# flyght.net
KiCad netlist of a schematic drawn in EAGLE
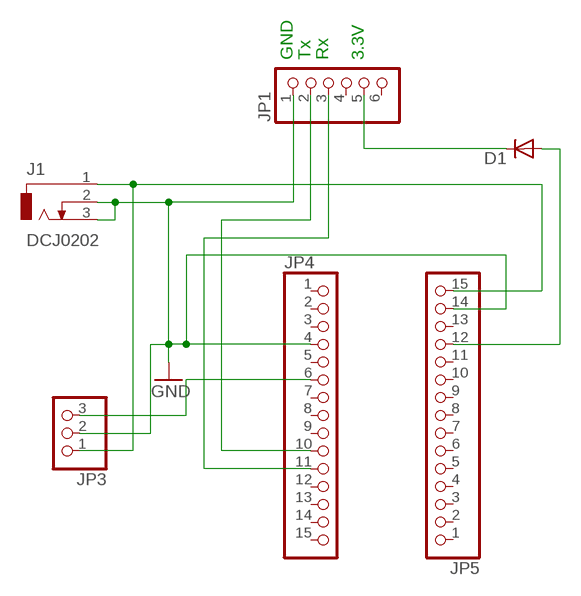
[diagram p0: schematic, sheet 1]

(export (version "E")
  (design (tool "Eeschema 10.0.6"))
  (components
    (comp (ref "D1")
      (value "1N4004")
      (footprint "eagle-import:DO41-10")
      (libsource (lib "eagle-import") (part "1N4004"))
    )
    (comp (ref "J1")
      (value "DCJ0202")
      (footprint "eagle-import:DCJ0202")
      (libsource (lib "eagle-import") (part "DCJ0202"))
    )
    (comp (ref "JP1")
      (value "PINHD-1X6")
      (footprint "eagle-import:1X06")
      (libsource (lib "eagle-import") (part "PINHD-1X6"))
    )
    (comp (ref "JP3")
      (value "PINHD-1X3")
      (footprint "eagle-import:1X03")
      (libsource (lib "eagle-import") (part "PINHD-1X3"))
    )
    (comp (ref "JP4")
      (value "PINHD-1X15")
      (footprint "eagle-import:1X15")
      (libsource (lib "eagle-import") (part "PINHD-1X15"))
    )
    (comp (ref "JP5")
      (value "PINHD-1X15")
      (footprint "eagle-import:1X15")
      (libsource (lib "eagle-import") (part "PINHD-1X15"))
    )
  )
  (nets
    (net (code "1") (name "GND") (class "Default")
      (node (ref "J1") (pin "2") (pinfunction "2_2") (pintype "passive"))
      (node (ref "J1") (pin "3") (pinfunction "3_3") (pintype "passive"))
      (node (ref "JP1") (pin "1") (pinfunction "1_1") (pintype "passive"))
      (node (ref "JP3") (pin "2") (pinfunction "2_2") (pintype "passive"))
      (node (ref "JP4") (pin "4") (pinfunction "4_4") (pintype "passive"))
      (node (ref "JP5") (pin "14") (pinfunction "14_14") (pintype "passive"))
    )
    (net (code "2") (name "Net-(D1-PadA)") (class "Default")
      (node (ref "D1") (pin "A") (pinfunction "A_A") (pintype "passive"))
      (node (ref "JP5") (pin "12") (pinfunction "12_12") (pintype "passive"))
    )
    (net (code "3") (name "Net-(D1-PadC)") (class "Default")
      (node (ref "D1") (pin "C") (pinfunction "C_C") (pintype "passive"))
      (node (ref "JP1") (pin "5") (pinfunction "5_5") (pintype "passive"))
    )
    (net (code "4") (name "Net-(J1-Pad1)") (class "Default")
      (node (ref "J1") (pin "1") (pinfunction "1_1") (pintype "passive"))
      (node (ref "JP3") (pin "1") (pinfunction "1_1") (pintype "passive"))
      (node (ref "JP5") (pin "15") (pinfunction "15_15") (pintype "passive"))
    )
    (net (code "5") (name "Net-(JP1-Pad2)") (class "Default")
      (node (ref "JP1") (pin "2") (pinfunction "2_2") (pintype "passive"))
      (node (ref "JP4") (pin "10") (pinfunction "10_10") (pintype "passive"))
    )
    (net (code "6") (name "Net-(JP1-Pad3)") (class "Default")
      (node (ref "JP1") (pin "3") (pinfunction "3_3") (pintype "passive"))
      (node (ref "JP4") (pin "11") (pinfunction "11_11") (pintype "passive"))
    )
    (net (code "7") (name "Net-(JP3-Pad3)") (class "Default")
      (node (ref "JP3") (pin "3") (pinfunction "3_3") (pintype "passive"))
      (node (ref "JP4") (pin "6") (pinfunction "6_6") (pintype "passive"))
    )
    (net (code "8") (name "unconnected-(JP1-Pad4)") (class "Default")
      (node (ref "JP1") (pin "4") (pinfunction "4_4") (pintype "passive"))
    )
    (net (code "9") (name "unconnected-(JP1-Pad6)") (class "Default")
      (node (ref "JP1") (pin "6") (pinfunction "6_6") (pintype "passive"))
    )
    (net (code "10") (name "unconnected-(JP4-Pad1)") (class "Default")
      (node (ref "JP4") (pin "1") (pinfunction "1_1") (pintype "passive"))
    )
    (net (code "11") (name "unconnected-(JP4-Pad2)") (class "Default")
      (node (ref "JP4") (pin "2") (pinfunction "2_2") (pintype "passive"))
    )
    (net (code "12") (name "unconnected-(JP4-Pad3)") (class "Default")
      (node (ref "JP4") (pin "3") (pinfunction "3_3") (pintype "passive"))
    )
    (net (code "13") (name "unconnected-(JP4-Pad5)") (class "Default")
      (node (ref "JP4") (pin "5") (pinfunction "5_5") (pintype "passive"))
    )
    (net (code "14") (name "unconnected-(JP4-Pad7)") (class "Default")
      (node (ref "JP4") (pin "7") (pinfunction "7_7") (pintype "passive"))
    )
    (net (code "15") (name "unconnected-(JP4-Pad8)") (class "Default")
      (node (ref "JP4") (pin "8") (pinfunction "8_8") (pintype "passive"))
    )
    (net (code "16") (name "unconnected-(JP4-Pad9)") (class "Default")
      (node (ref "JP4") (pin "9") (pinfunction "9_9") (pintype "passive"))
    )
    (net (code "17") (name "unconnected-(JP4-Pad12)") (class "Default")
      (node (ref "JP4") (pin "12") (pinfunction "12_12") (pintype "passive"))
    )
    (net (code "18") (name "unconnected-(JP4-Pad13)") (class "Default")
      (node (ref "JP4") (pin "13") (pinfunction "13_13") (pintype "passive"))
    )
    (net (code "19") (name "unconnected-(JP4-Pad14)") (class "Default")
      (node (ref "JP4") (pin "14") (pinfunction "14_14") (pintype "passive"))
    )
    (net (code "20") (name "unconnected-(JP4-Pad15)") (class "Default")
      (node (ref "JP4") (pin "15") (pinfunction "15_15") (pintype "passive"))
    )
    (net (code "21") (name "unconnected-(JP5-Pad1)") (class "Default")
      (node (ref "JP5") (pin "1") (pinfunction "1_1") (pintype "passive"))
    )
    (net (code "22") (name "unconnected-(JP5-Pad2)") (class "Default")
      (node (ref "JP5") (pin "2") (pinfunction "2_2") (pintype "passive"))
    )
    (net (code "23") (name "unconnected-(JP5-Pad3)") (class "Default")
      (node (ref "JP5") (pin "3") (pinfunction "3_3") (pintype "passive"))
    )
    (net (code "24") (name "unconnected-(JP5-Pad4)") (class "Default")
      (node (ref "JP5") (pin "4") (pinfunction "4_4") (pintype "passive"))
    )
    (net (code "25") (name "unconnected-(JP5-Pad5)") (class "Default")
      (node (ref "JP5") (pin "5") (pinfunction "5_5") (pintype "passive"))
    )
    (net (code "26") (name "unconnected-(JP5-Pad6)") (class "Default")
      (node (ref "JP5") (pin "6") (pinfunction "6_6") (pintype "passive"))
    )
    (net (code "27") (name "unconnected-(JP5-Pad7)") (class "Default")
      (node (ref "JP5") (pin "7") (pinfunction "7_7") (pintype "passive"))
    )
    (net (code "28") (name "unconnected-(JP5-Pad8)") (class "Default")
      (node (ref "JP5") (pin "8") (pinfunction "8_8") (pintype "passive"))
    )
    (net (code "29") (name "unconnected-(JP5-Pad9)") (class "Default")
      (node (ref "JP5") (pin "9") (pinfunction "9_9") (pintype "passive"))
    )
    (net (code "30") (name "unconnected-(JP5-Pad10)") (class "Default")
      (node (ref "JP5") (pin "10") (pinfunction "10_10") (pintype "passive"))
    )
    (net (code "31") (name "unconnected-(JP5-Pad11)") (class "Default")
      (node (ref "JP5") (pin "11") (pinfunction "11_11") (pintype "passive"))
    )
    (net (code "32") (name "unconnected-(JP5-Pad13)") (class "Default")
      (node (ref "JP5") (pin "13") (pinfunction "13_13") (pintype "passive"))
    )
  )
)
